# ProPrj_555_Circuit_2025-11-02.net
KiCad netlist of a schematic drawn in EasyEDA Pro
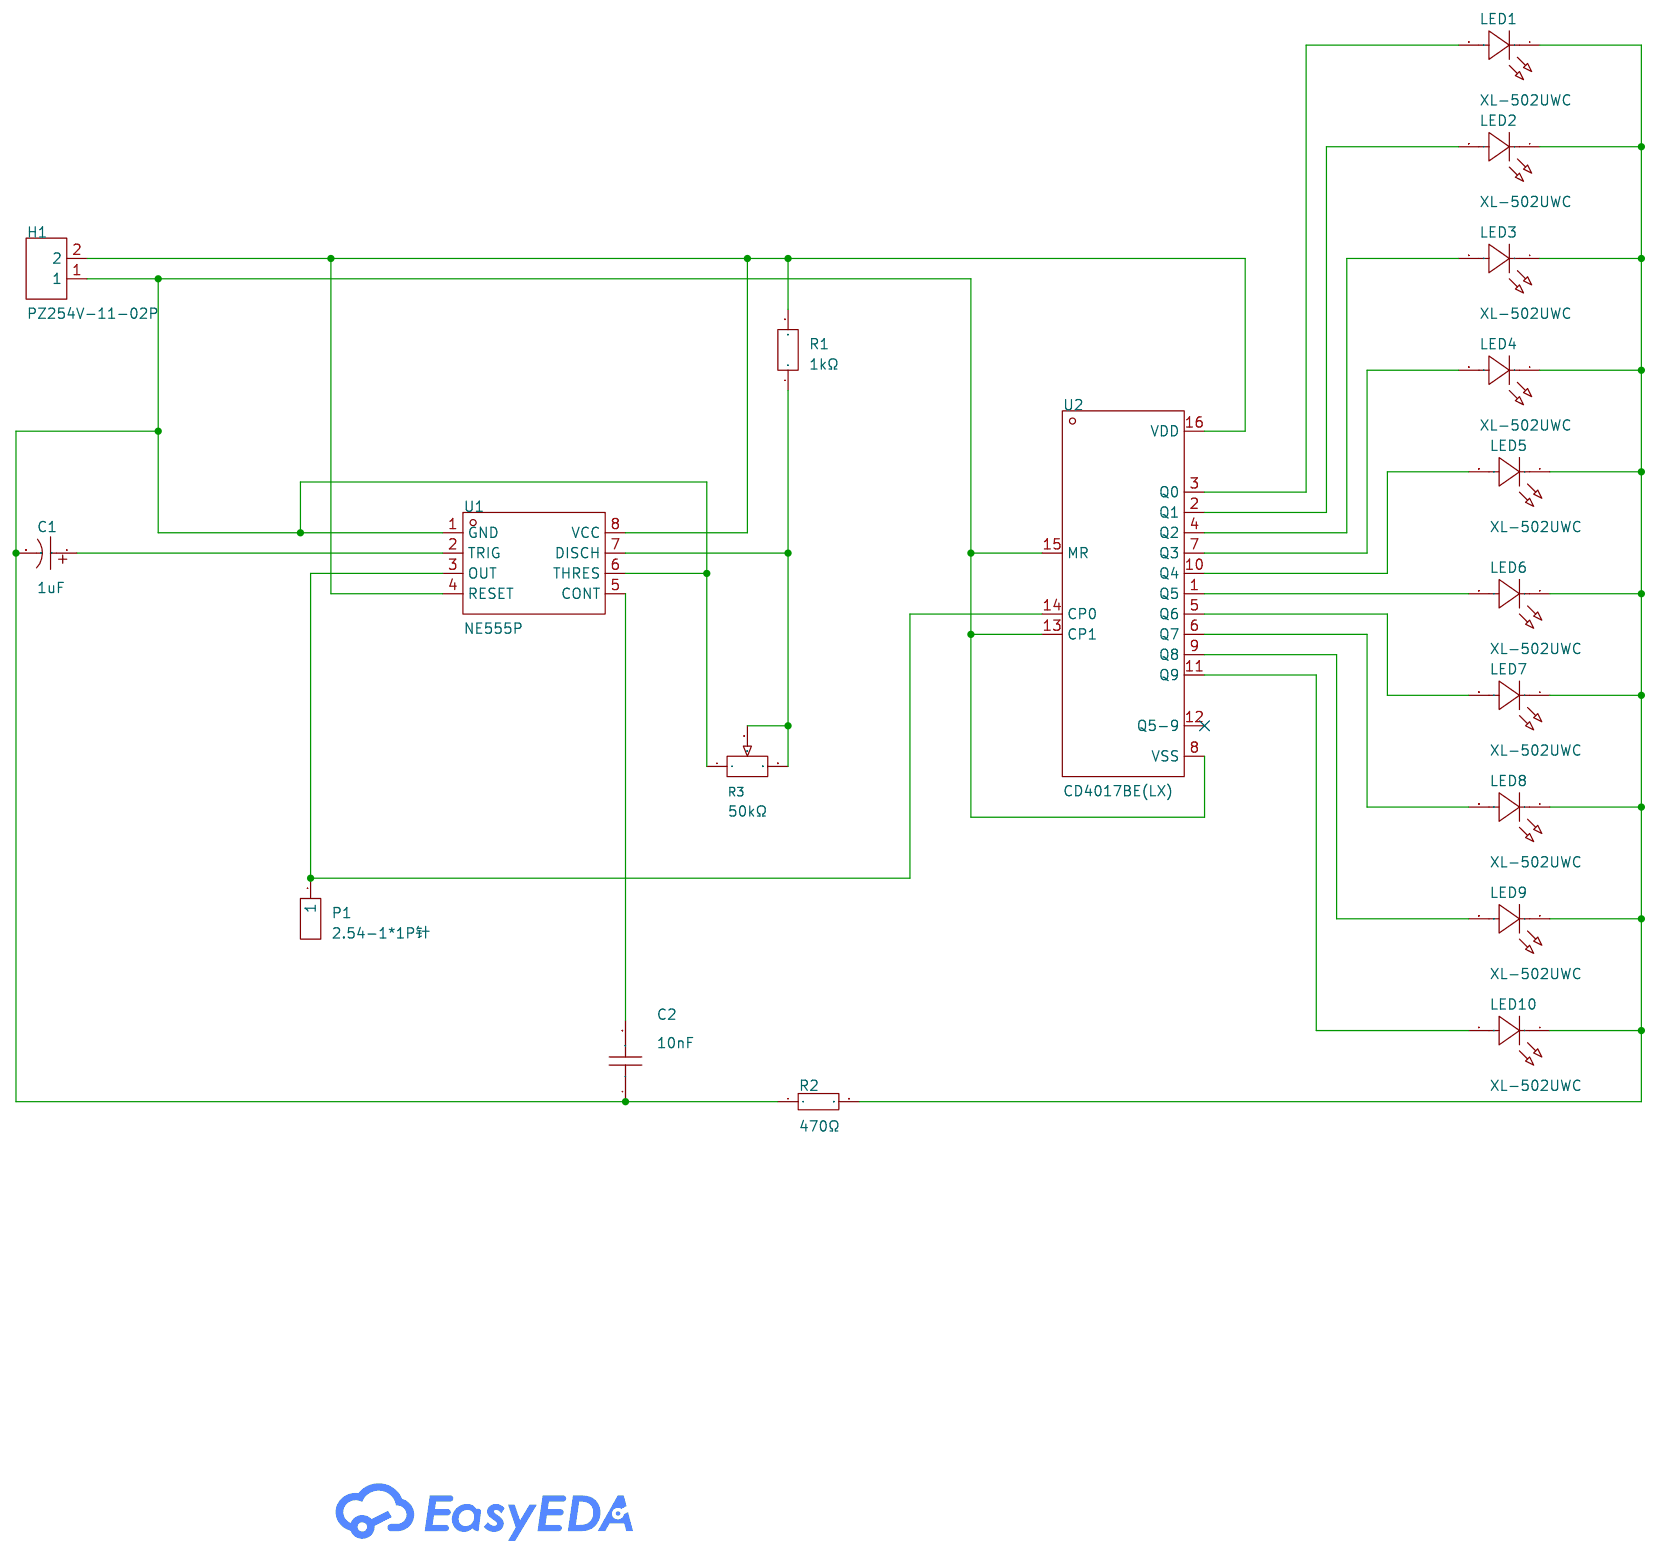
[diagram p0: schematic sheet]

(export (version "E")
  (design (tool "Eeschema 10.0.6"))
  (components
    (comp (ref "C1")
      (value "1uF")
      (footprint "easyedapro:CAP-TH_BD5.0-P2.00-D0.8-FD")
      (fields (field (name "Manufacturer Part") "KF010M050C110A") (field (name "Manufacturer") "CapXon(丰宾)"))
      (libsource (lib "easyedapro") (part "KF010M050C110A"))
    )
    (comp (ref "C2")
      (value "10nF")
      (footprint "easyedapro:CAP-TH_L8.0-W4.0-P5.00-D1.2")
      (fields (field (name "Manufacturer Part") "N09F1B103MN0B0S0N0") (field (name "Manufacturer") "STE(松田)"))
      (libsource (lib "easyedapro") (part "N09F1B103MN0B0S0N0"))
    )
    (comp (ref "H1")
      (value "PZ254V-11-02P")
      (footprint "easyedapro:HDR-TH_2P-P2.54-V-M")
      (fields (field (name "Manufacturer") "XFCN(兴飞)"))
      (libsource (lib "easyedapro") (part "PZ254V-11-02P"))
    )
    (comp (ref "LED1")
      (value "XL-502UWC")
      (footprint "easyedapro:LED-TH_BD5.9-P2.54-RD_WHITE")
      (fields (field (name "Manufacturer") "XINGLIGHT(成兴光)"))
      (libsource (lib "easyedapro") (part "XL-502UWC"))
    )
    (comp (ref "LED2")
      (value "XL-502UWC")
      (footprint "easyedapro:LED-TH_BD5.9-P2.54-RD_WHITE")
      (fields (field (name "Manufacturer") "XINGLIGHT(成兴光)"))
      (libsource (lib "easyedapro") (part "XL-502UWC"))
    )
    (comp (ref "LED3")
      (value "XL-502UWC")
      (footprint "easyedapro:LED-TH_BD5.9-P2.54-RD_WHITE")
      (fields (field (name "Manufacturer") "XINGLIGHT(成兴光)"))
      (libsource (lib "easyedapro") (part "XL-502UWC"))
    )
    (comp (ref "LED4")
      (value "XL-502UWC")
      (footprint "easyedapro:LED-TH_BD5.9-P2.54-RD_WHITE")
      (fields (field (name "Manufacturer") "XINGLIGHT(成兴光)"))
      (libsource (lib "easyedapro") (part "XL-502UWC"))
    )
    (comp (ref "LED5")
      (value "XL-502UWC")
      (footprint "easyedapro:LED-TH_BD5.9-P2.54-RD_WHITE")
      (fields (field (name "Manufacturer") "XINGLIGHT(成兴光)"))
      (libsource (lib "easyedapro") (part "XL-502UWC"))
    )
    (comp (ref "LED6")
      (value "XL-502UWC")
      (footprint "easyedapro:LED-TH_BD5.9-P2.54-RD_WHITE")
      (fields (field (name "Manufacturer") "XINGLIGHT(成兴光)"))
      (libsource (lib "easyedapro") (part "XL-502UWC"))
    )
    (comp (ref "LED7")
      (value "XL-502UWC")
      (footprint "easyedapro:LED-TH_BD5.9-P2.54-RD_WHITE")
      (fields (field (name "Manufacturer") "XINGLIGHT(成兴光)"))
      (libsource (lib "easyedapro") (part "XL-502UWC"))
    )
    (comp (ref "LED8")
      (value "XL-502UWC")
      (footprint "easyedapro:LED-TH_BD5.9-P2.54-RD_WHITE")
      (fields (field (name "Manufacturer") "XINGLIGHT(成兴光)"))
      (libsource (lib "easyedapro") (part "XL-502UWC"))
    )
    (comp (ref "LED9")
      (value "XL-502UWC")
      (footprint "easyedapro:LED-TH_BD5.9-P2.54-RD_WHITE")
      (fields (field (name "Manufacturer") "XINGLIGHT(成兴光)"))
      (libsource (lib "easyedapro") (part "XL-502UWC"))
    )
    (comp (ref "LED10")
      (value "XL-502UWC")
      (footprint "easyedapro:LED-TH_BD5.9-P2.54-RD_WHITE")
      (fields (field (name "Manufacturer") "XINGLIGHT(成兴光)"))
      (libsource (lib "easyedapro") (part "XL-502UWC"))
    )
    (comp (ref "P1")
      (value "2.54-1*1P针")
      (footprint "easyedapro:HDR-TH_1P-P2.54-V-M")
      (fields (field (name "Manufacturer") "BOOMELE(博穆精密)"))
      (libsource (lib "easyedapro") (part "Header-Male-2.54_1x1"))
    )
    (comp (ref "R1")
      (value "1kΩ")
      (footprint "easyedapro:RES-TH_BD2.3-L6.5-P10.50-D0.5")
      (fields (field (name "Manufacturer Part") "MF1/4W-1KΩ±1%T52") (field (name "Manufacturer") "华星机电"))
      (libsource (lib "easyedapro") (part "MF1/4W-1KΩ±1%T52"))
    )
    (comp (ref "R2")
      (value "470Ω")
      (footprint "easyedapro:RES-TH_BD2.2-L6.5-P10.50-D0.6")
      (fields
        (field (name "Manufacturer Part") "MFR0W4F4700A50")
        (field (name "Manufacturer") "UNI-ROYAL(厚声)")
      )
      (libsource (lib "easyedapro") (part "MFR0W4F4700A50"))
    )
    (comp (ref "R3")
      (value "50kΩ")
      (footprint "easyedapro:RES-ADJ-TH_3P-L9.5-W4.85-P2.50-BL-L")
      (fields (field (name "Manufacturer Part") "3296X-1-503") (field (name "Manufacturer") "BOCHEN(博晨)"))
      (libsource (lib "easyedapro") (part "3296X-1-503_C118912"))
    )
    (comp (ref "U1")
      (value "NE555P")
      (footprint "easyedapro:DIP-8_L9.8-W6.6-P2.54-LS7.6-BL")
      (fields (field (name "Manufacturer") "TI(德州仪器)"))
      (libsource (lib "easyedapro") (part "NE555P"))
    )
    (comp (ref "U2")
      (value "CD4017BE(LX)")
      (footprint "easyedapro:PDIP-16_L19.3-W6.4-P2.54-LS7.94-BL")
      (fields (field (name "Manufacturer") "LX(灵星芯微)"))
      (libsource (lib "easyedapro") (part "CD4017BE(LX)"))
    )
  )
  (nets
    (net (code "1") (name "Net-(LED1-A)") (class "Default")
      (node (ref "LED1") (pin "2") (pinfunction "A_2") (pintype "unspecified"))
      (node (ref "U2") (pin "3") (pinfunction "Q0_3") (pintype "unspecified"))
    )
    (net (code "2") (name "Net-(LED1-K)") (class "Default")
      (node (ref "LED1") (pin "1") (pinfunction "K_1") (pintype "unspecified"))
      (node (ref "LED10") (pin "1") (pinfunction "K_1") (pintype "unspecified"))
      (node (ref "LED2") (pin "1") (pinfunction "K_1") (pintype "unspecified"))
      (node (ref "LED3") (pin "1") (pinfunction "K_1") (pintype "unspecified"))
      (node (ref "LED4") (pin "1") (pinfunction "K_1") (pintype "unspecified"))
      (node (ref "LED5") (pin "1") (pinfunction "K_1") (pintype "unspecified"))
      (node (ref "LED6") (pin "1") (pinfunction "K_1") (pintype "unspecified"))
      (node (ref "LED7") (pin "1") (pinfunction "K_1") (pintype "unspecified"))
      (node (ref "LED8") (pin "1") (pinfunction "K_1") (pintype "unspecified"))
      (node (ref "LED9") (pin "1") (pinfunction "K_1") (pintype "unspecified"))
      (node (ref "R2") (pin "2") (pinfunction "2_2") (pintype "input"))
    )
    (net (code "3") (name "Net-(LED2-A)") (class "Default")
      (node (ref "LED2") (pin "2") (pinfunction "A_2") (pintype "unspecified"))
      (node (ref "U2") (pin "2") (pinfunction "Q1_2") (pintype "unspecified"))
    )
    (net (code "4") (name "Net-(LED3-A)") (class "Default")
      (node (ref "LED3") (pin "2") (pinfunction "A_2") (pintype "unspecified"))
      (node (ref "U2") (pin "4") (pinfunction "Q2_4") (pintype "unspecified"))
    )
    (net (code "5") (name "Net-(LED4-A)") (class "Default")
      (node (ref "LED4") (pin "2") (pinfunction "A_2") (pintype "unspecified"))
      (node (ref "U2") (pin "7") (pinfunction "Q3_7") (pintype "unspecified"))
    )
    (net (code "6") (name "Net-(LED5-A)") (class "Default")
      (node (ref "LED5") (pin "2") (pinfunction "A_2") (pintype "unspecified"))
      (node (ref "U2") (pin "10") (pinfunction "Q4_10") (pintype "unspecified"))
    )
    (net (code "7") (name "Net-(LED6-A)") (class "Default")
      (node (ref "LED6") (pin "2") (pinfunction "A_2") (pintype "unspecified"))
      (node (ref "U2") (pin "1") (pinfunction "Q5_1") (pintype "unspecified"))
    )
    (net (code "8") (name "Net-(LED7-A)") (class "Default")
      (node (ref "LED7") (pin "2") (pinfunction "A_2") (pintype "unspecified"))
      (node (ref "U2") (pin "5") (pinfunction "Q6_5") (pintype "unspecified"))
    )
    (net (code "9") (name "Net-(LED8-A)") (class "Default")
      (node (ref "LED8") (pin "2") (pinfunction "A_2") (pintype "unspecified"))
      (node (ref "U2") (pin "6") (pinfunction "Q7_6") (pintype "unspecified"))
    )
    (net (code "10") (name "Net-(LED9-A)") (class "Default")
      (node (ref "LED9") (pin "2") (pinfunction "A_2") (pintype "unspecified"))
      (node (ref "U2") (pin "9") (pinfunction "Q8_9") (pintype "unspecified"))
    )
    (net (code "11") (name "Net-(LED10-A)") (class "Default")
      (node (ref "LED10") (pin "2") (pinfunction "A_2") (pintype "unspecified"))
      (node (ref "U2") (pin "11") (pinfunction "Q9_11") (pintype "unspecified"))
    )
    (net (code "12") (name "Net-(U1-CONT)") (class "Default")
      (node (ref "C2") (pin "2") (pinfunction "2_2") (pintype "unspecified"))
      (node (ref "U1") (pin "5") (pinfunction "CONT_5") (pintype "input"))
    )
    (net (code "13") (name "Net-(U1-DISCH)") (class "Default")
      (node (ref "R1") (pin "1") (pinfunction "1_1") (pintype "unspecified"))
      (node (ref "R3") (pin "2") (pinfunction "2_2") (pintype "input"))
      (node (ref "R3") (pin "3") (pinfunction "3_3") (pintype "input"))
      (node (ref "U1") (pin "7") (pinfunction "DISCH_7") (pintype "input"))
    )
    (net (code "14") (name "Net-(U1-GND)") (class "Default")
      (node (ref "C1") (pin "2") (pinfunction "2_2") (pintype "input"))
      (node (ref "C2") (pin "1") (pinfunction "1_1") (pintype "unspecified"))
      (node (ref "H1") (pin "1") (pinfunction "1_1") (pintype "unspecified"))
      (node (ref "R2") (pin "1") (pinfunction "1_1") (pintype "input"))
      (node (ref "R3") (pin "1") (pinfunction "1_1") (pintype "input"))
      (node (ref "U1") (pin "1") (pinfunction "GND_1") (pintype "input"))
      (node (ref "U1") (pin "6") (pinfunction "THRES_6") (pintype "input"))
      (node (ref "U2") (pin "13") (pinfunction "CP1_13") (pintype "unspecified"))
      (node (ref "U2") (pin "15") (pinfunction "MR_15") (pintype "unspecified"))
      (node (ref "U2") (pin "8") (pinfunction "VSS_8") (pintype "unspecified"))
    )
    (net (code "15") (name "Net-(U1-OUT)") (class "Default")
      (node (ref "P1") (pin "1") (pinfunction "1_1") (pintype "input"))
      (node (ref "U1") (pin "3") (pinfunction "OUT_3") (pintype "input"))
      (node (ref "U2") (pin "14") (pinfunction "CP0_14") (pintype "unspecified"))
    )
    (net (code "16") (name "Net-(U1-RESET)") (class "Default")
      (node (ref "H1") (pin "2") (pinfunction "2_2") (pintype "unspecified"))
      (node (ref "R1") (pin "2") (pinfunction "2_2") (pintype "unspecified"))
      (node (ref "U1") (pin "4") (pinfunction "RESET_4") (pintype "input"))
      (node (ref "U1") (pin "8") (pinfunction "VCC_8") (pintype "input"))
      (node (ref "U2") (pin "16") (pinfunction "VDD_16") (pintype "unspecified"))
    )
    (net (code "17") (name "Net-(U1-TRIG)") (class "Default")
      (node (ref "C1") (pin "1") (pinfunction "1_1") (pintype "input"))
      (node (ref "U1") (pin "2") (pinfunction "TRIG_2") (pintype "input"))
    )
    (net (code "18") (name "unconnected-(U2-Q5-9-Pad12)") (class "Default")
      (node (ref "U2") (pin "12") (pinfunction "Q5-9_12") (pintype "unspecified+no_connect"))
    )
  )
)
